# MCP3425-1.net
KiCad netlist of a schematic drawn in EAGLE
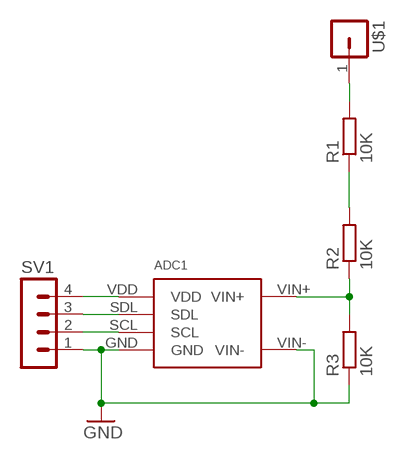
[diagram p0: schematic, sheet 1]

(export (version "E")
  (design (tool "Eeschema 10.0.6"))
  (components
    (comp (ref "ADC1")
      (value "MCP3425MOD")
      (footprint "eagle-import:MCP3425MOD")
      (libsource (lib "eagle-import") (part "MCP3425MOD"))
    )
    (comp (ref "R1")
      (value "10K")
      (footprint "eagle-import:0204_5")
      (libsource (lib "eagle-import") (part "R-EU_0204/5"))
    )
    (comp (ref "R2")
      (value "10K")
      (footprint "eagle-import:0204_5")
      (libsource (lib "eagle-import") (part "R-EU_0204/5"))
    )
    (comp (ref "R3")
      (value "10K")
      (footprint "eagle-import:0204_5")
      (libsource (lib "eagle-import") (part "R-EU_0204/5"))
    )
    (comp (ref "SV1")
      (value "PINHEAD-MA04-1")
      (footprint "eagle-import:PINHEAD-MA04-1")
      (libsource (lib "eagle-import") (part "PINHEAD-MA04-1"))
    )
    (comp (ref "U$1")
      (value "PINHEAD-MA01-1")
      (footprint "eagle-import:PINHEAD-MA01-1")
      (libsource (lib "eagle-import") (part "PINHEAD-MA01-1"))
    )
  )
  (nets
    (net (code "1") (name "GND") (class "Default")
      (node (ref "ADC1") (pin "GND") (pinfunction "GND_GND") (pintype "bidirectional"))
      (node (ref "ADC1") (pin "VIN-") (pinfunction "VIN-_VIN-") (pintype "bidirectional"))
      (node (ref "R3") (pin "1") (pinfunction "1_1") (pintype "passive"))
      (node (ref "SV1") (pin "1") (pinfunction "1_1") (pintype "passive"))
    )
    (net (code "2") (name "Net-(ADC1-PadSCL)") (class "Default")
      (node (ref "ADC1") (pin "SCL") (pinfunction "SCL_SCL") (pintype "bidirectional"))
      (node (ref "SV1") (pin "2") (pinfunction "2_2") (pintype "passive"))
    )
    (net (code "3") (name "Net-(ADC1-PadSDL)") (class "Default")
      (node (ref "ADC1") (pin "SDL") (pinfunction "SDL_SDL") (pintype "bidirectional"))
      (node (ref "SV1") (pin "3") (pinfunction "3_3") (pintype "passive"))
    )
    (net (code "4") (name "Net-(ADC1-PadVDD)") (class "Default")
      (node (ref "ADC1") (pin "VDD") (pinfunction "VDD_VDD") (pintype "bidirectional"))
      (node (ref "SV1") (pin "4") (pinfunction "4_4") (pintype "passive"))
    )
    (net (code "5") (name "Net-(ADC1-PadVIN+)") (class "Default")
      (node (ref "ADC1") (pin "VIN+") (pinfunction "VIN+_VIN+") (pintype "bidirectional"))
      (node (ref "R2") (pin "1") (pinfunction "1_1") (pintype "passive"))
      (node (ref "R3") (pin "2") (pinfunction "2_2") (pintype "passive"))
    )
    (net (code "6") (name "Net-(R1-Pad1)") (class "Default")
      (node (ref "R1") (pin "1") (pinfunction "1_1") (pintype "passive"))
      (node (ref "R2") (pin "2") (pinfunction "2_2") (pintype "passive"))
    )
    (net (code "7") (name "Net-(R1-Pad2)") (class "Default")
      (node (ref "R1") (pin "2") (pinfunction "2_2") (pintype "passive"))
      (node (ref "U$1") (pin "1") (pinfunction "1_1") (pintype "passive"))
    )
  )
)
